# PR9022.net
KiCad netlist of a schematic drawn in EAGLE
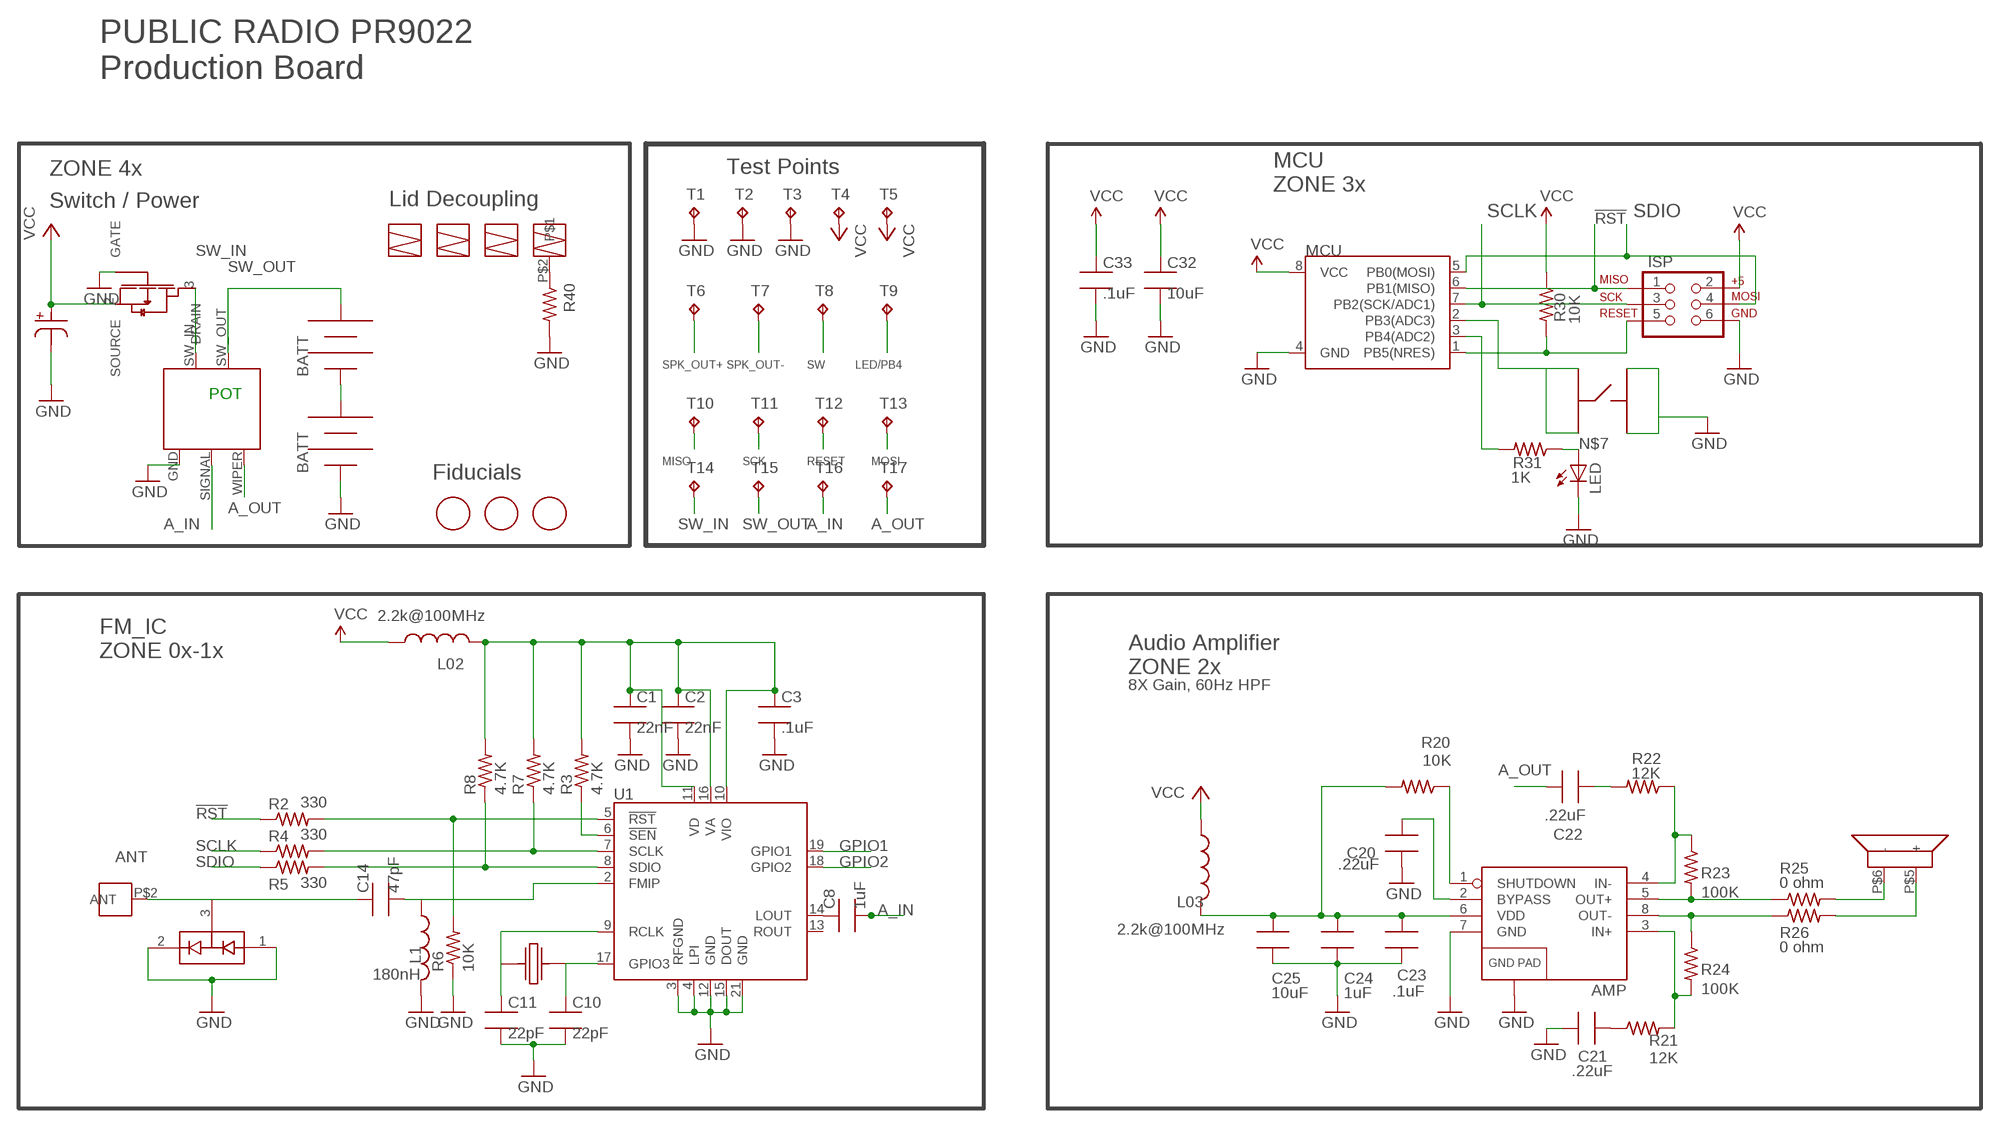
[diagram p0: schematic, sheet 1]

(export (version "E")
  (design (tool "Eeschema 10.0.6"))
  (components
    (comp (ref "AMP")
      (value "TPA6203A1")
      (footprint "eagle-import:8-MSOP")
      (libsource (lib "eagle-import") (part "TPA6203A1"))
    )
    (comp (ref "ANT_MOUNT")
      (value "DNP")
      (footprint "eagle-import:PEM_M3")
      (libsource (lib "eagle-import") (part "M3_PEMNUT"))
    )
    (comp (ref "C1")
      (value "22nF")
      (footprint "eagle-import:0603_CPL")
      (fields
        (field (name "MFG_PN") "CL10B223KB8NNNC")
        (field (name "TOL") "10%")
        (field (name "VOLTAGE") "16V")
      )
      (libsource (lib "eagle-import") (part "C_SMT_0603_CPL"))
    )
    (comp (ref "C2")
      (value "22nF")
      (footprint "eagle-import:0603_CPL")
      (fields
        (field (name "MFG_PN") "CL10B223KB8NNNC")
        (field (name "TOL") "10%")
        (field (name "VOLTAGE") "16V")
      )
      (libsource (lib "eagle-import") (part "C_SMT_0603_CPL"))
    )
    (comp (ref "C3")
      (value ".1uF")
      (footprint "eagle-import:0603_CPL")
      (fields
        (field (name "MFG_PN") "CL10B104KB8SFNC")
        (field (name "TOL") "10%")
        (field (name "VOLTAGE") "16V")
      )
      (libsource (lib "eagle-import") (part "C_SMT_0603_CPL"))
    )
    (comp (ref "C8")
      (value "1uF")
      (footprint "eagle-import:0603_CPL")
      (fields
        (field (name "MFG_PN") "CL10B105KP8NNNC")
        (field (name "TOL") "10%")
        (field (name "VOLTAGE") "10V")
      )
      (libsource (lib "eagle-import") (part "C_SMT_0603_CPL"))
    )
    (comp (ref "C10")
      (value "22pF")
      (footprint "eagle-import:0603_CPL")
      (fields
        (field (name "MFG_PN") "C1608C0G1H220J080AA")
        (field (name "TOL") "5%")
        (field (name "VOLTAGE") "50V")
      )
      (libsource (lib "eagle-import") (part "C_SMT_0603_CPL"))
    )
    (comp (ref "C11")
      (value "22pF")
      (footprint "eagle-import:0603_CPL")
      (fields
        (field (name "MFG_PN") "C1608C0G1H220J080AA")
        (field (name "TOL") "5%")
        (field (name "VOLTAGE") "50V")
      )
      (libsource (lib "eagle-import") (part "C_SMT_0603_CPL"))
    )
    (comp (ref "C14")
      (value "47pF")
      (footprint "eagle-import:0603_CPL")
      (fields
        (field (name "MFG_PN") "CL10C470JB8NCNC")
        (field (name "TOL") "5%")
        (field (name "VOLTAGE") "50V")
      )
      (libsource (lib "eagle-import") (part "C_SMT_0603_CPL"))
    )
    (comp (ref "C20")
      (value ".22uF")
      (footprint "eagle-import:0603_CPL")
      (fields
        (field (name "MFG_PN") "C1608X7R1C224K080AC")
        (field (name "TOL") "10%")
        (field (name "VOLTAGE") "16V")
      )
      (libsource (lib "eagle-import") (part "C_SMT_0603_CPL"))
    )
    (comp (ref "C21")
      (value ".22uF")
      (footprint "eagle-import:0603_CPL")
      (fields
        (field (name "MFG_PN") "C1608X7R1C224K080AC")
        (field (name "TOL") "10%")
        (field (name "VOLTAGE") "16V")
      )
      (libsource (lib "eagle-import") (part "C_SMT_0603_CPL"))
    )
    (comp (ref "C22")
      (value ".22uF")
      (footprint "eagle-import:0603_CPL")
      (fields
        (field (name "MFG_PN") "C1608X7R1C224K080AC")
        (field (name "TOL") "10%")
        (field (name "VOLTAGE") "16V")
      )
      (libsource (lib "eagle-import") (part "C_SMT_0603_CPL"))
    )
    (comp (ref "C23")
      (value ".1uF")
      (footprint "eagle-import:0603_CPL")
      (fields
        (field (name "MFG_PN") "CL10B104KB8SFNC")
        (field (name "TOL") "10%")
        (field (name "VOLTAGE") "16V")
      )
      (libsource (lib "eagle-import") (part "C_SMT_0603_CPL"))
    )
    (comp (ref "C24")
      (value "1uF")
      (footprint "eagle-import:0603_CPL")
      (fields
        (field (name "MFG_PN") "CL10B105KP8NNNC")
        (field (name "TOL") "10%")
        (field (name "VOLTAGE") "10V")
      )
      (libsource (lib "eagle-import") (part "C_SMT_0603_CPL"))
    )
    (comp (ref "C25")
      (value "10uF")
      (footprint "eagle-import:0603_CPL")
      (fields
        (field (name "MFG_PN") "CL10A106MQ8NNNC")
        (field (name "TOL") "20%")
        (field (name "VOLTAGE") "6.3V")
      )
      (libsource (lib "eagle-import") (part "C_SMT_0603_CPL"))
    )
    (comp (ref "C32")
      (value "10uF")
      (footprint "eagle-import:0603_CPL")
      (fields
        (field (name "MFG_PN") "CL10A106MQ8NNNC")
        (field (name "TOL") "20%")
        (field (name "VOLTAGE") "6.3V")
      )
      (libsource (lib "eagle-import") (part "C_SMT_0603_CPL"))
    )
    (comp (ref "C33")
      (value ".1uF")
      (footprint "eagle-import:0603_CPL")
      (fields
        (field (name "MFG_PN") "CL10B104KB8SFNC")
        (field (name "TOL") "10%")
        (field (name "VOLTAGE") "16V")
      )
      (libsource (lib "eagle-import") (part "C_SMT_0603_CPL"))
    )
    (comp (ref "C40")
      (value "220uF")
      (footprint "eagle-import:NICHICON_UD_63")
      (fields (field (name "TOL") "20%") (field (name "VOLTAGE") "16V"))
      (libsource (lib "eagle-import") (part "NICHICON_SERIESUD"))
    )
    (comp (ref "D1")
      (value "BAV99")
      (footprint "eagle-import:SOT23_CPL")
      (fields (field (name "MFG_PN") "BAV99,215"))
      (libsource (lib "eagle-import") (part "BAV99"))
    )
    (comp (ref "FET1")
      (value "AO3435")
      (footprint "eagle-import:SOT23_CPL")
      (fields (field (name "MFG_PN") "AO3435"))
      (libsource (lib "eagle-import") (part "AO3435"))
    )
    (comp (ref "ISP")
      (value "AVR_SPI_PRG_6NS")
      (footprint "eagle-import:2X3-NS")
      (libsource (lib "eagle-import") (part "AVR_SPI_PRG_6NS"))
    )
    (comp (ref "JP5")
      (value "BK-92_MPD_AA_BATT_CLIP")
      (footprint "eagle-import:BK92_AA_BATT")
      (fields (field (name "MFG_PN") "2 of BK92 - supplied by CL Labs"))
      (libsource (lib "eagle-import") (part "BK-92_MPD_AA_BATT_CLIP"))
    )
    (comp (ref "JP6")
      (value "BK-92_MPD_AA_BATT_CLIP")
      (footprint "eagle-import:BK92_AA_BATT")
      (fields (field (name "MFG_PN") "2 of BK92 - supplied by CL Labs"))
      (libsource (lib "eagle-import") (part "BK-92_MPD_AA_BATT_CLIP"))
    )
    (comp (ref "L1")
      (value "180nH")
      (footprint "eagle-import:0805_ADAFRUIT")
      (fields
        (field (name "CURRENT") "400mA")
        (field (name "DCR") "640m")
        (field (name "MFG_PN") "AISC-0805-R18J-T")
        (field (name "TOL") "5%")
      )
      (libsource (lib "eagle-import") (part "L_SMT_0805_ADAFRUIT"))
    )
    (comp (ref "L02")
      (value "2.2k@100MHz")
      (footprint "eagle-import:0603_CPL")
      (fields
        (field (name "CURRENT") "150mA")
        (field (name "DCR") "2.3")
        (field (name "MFG_PN") "HZ0603A222R-10")
      )
      (libsource (lib "eagle-import") (part "L_SMT_0603_CPL"))
    )
    (comp (ref "L03")
      (value "2.2k@100MHz")
      (footprint "eagle-import:0603_CPL")
      (fields
        (field (name "CURRENT") "150mA")
        (field (name "DCR") "2.3")
        (field (name "MFG_PN") "HZ0603A222R-10")
      )
      (libsource (lib "eagle-import") (part "L_SMT_0603_CPL"))
    )
    (comp (ref "LED")
      (value "LEDCHIPLED_0805")
      (footprint "eagle-import:CHIPLED_0805")
      (libsource (lib "eagle-import") (part "LEDCHIPLED_0805"))
    )
    (comp (ref "MARK1")
      (value "FIDUCIAL")
      (footprint "eagle-import:FIDUCIAL_1MM")
      (libsource (lib "eagle-import") (part "FIDUCIAL"))
    )
    (comp (ref "MARK2")
      (value "FIDUCIAL")
      (footprint "eagle-import:FIDUCIAL_1MM")
      (libsource (lib "eagle-import") (part "FIDUCIAL"))
    )
    (comp (ref "MARK3")
      (value "FIDUCIAL")
      (footprint "eagle-import:FIDUCIAL_1MM")
      (libsource (lib "eagle-import") (part "FIDUCIAL"))
    )
    (comp (ref "MCU")
      (value "ATTINY45TINY45-20-SMT")
      (footprint "eagle-import:8-SOIC")
      (libsource (lib "eagle-import") (part "ATTINY45TINY45-20-SMT"))
    )
    (comp (ref "R1")
      (value "RV170SF_TAIWANA_POT_SW")
      (footprint "eagle-import:RV170SF_SW_POT")
      (fields (field (name "MFG_PN") "RV170SF-43-20F-A10K - supplied by CL Labs"))
      (libsource (lib "eagle-import") (part "RV170SF_TAIWANA_POT_SW"))
    )
    (comp (ref "R2")
      (value "330")
      (footprint "eagle-import:0603_CPL")
      (fields (field (name "MFG_PN") "MCR03ERTJ331") (field (name "POWER") "1/10W") (field (name "TOL") "5%"))
      (libsource (lib "eagle-import") (part "R_SMT_R0603_CPL"))
    )
    (comp (ref "R3")
      (value "4.7K")
      (footprint "eagle-import:0603_CPL")
      (fields
        (field (name "MFG_PN") "ERJ-3EKF4701V")
        (field (name "POWER") "1/10W")
        (field (name "TOL") "1%")
      )
      (libsource (lib "eagle-import") (part "R_SMT_R0603_CPL"))
    )
    (comp (ref "R4")
      (value "330")
      (footprint "eagle-import:0603_CPL")
      (fields (field (name "MFG_PN") "MCR03ERTJ331") (field (name "POWER") "1/10W") (field (name "TOL") "5%"))
      (libsource (lib "eagle-import") (part "R_SMT_R0603_CPL"))
    )
    (comp (ref "R5")
      (value "330")
      (footprint "eagle-import:0603_CPL")
      (fields (field (name "MFG_PN") "MCR03ERTJ331") (field (name "POWER") "1/10W") (field (name "TOL") "5%"))
      (libsource (lib "eagle-import") (part "R_SMT_R0603_CPL"))
    )
    (comp (ref "R6")
      (value "10K")
      (footprint "eagle-import:0603_CPL")
      (fields
        (field (name "MFG_PN") "ERJ-3GEYJ103V")
        (field (name "POWER") "1/10W")
        (field (name "TOL") "5%")
      )
      (libsource (lib "eagle-import") (part "R_SMT_R0603_CPL"))
    )
    (comp (ref "R7")
      (value "4.7K")
      (footprint "eagle-import:0603_CPL")
      (fields
        (field (name "MFG_PN") "ERJ-3EKF4701V")
        (field (name "POWER") "1/10W")
        (field (name "TOL") "1%")
      )
      (libsource (lib "eagle-import") (part "R_SMT_R0603_CPL"))
    )
    (comp (ref "R8")
      (value "4.7K")
      (footprint "eagle-import:0603_CPL")
      (fields
        (field (name "MFG_PN") "ERJ-3EKF4701V")
        (field (name "POWER") "1/10W")
        (field (name "TOL") "1%")
      )
      (libsource (lib "eagle-import") (part "R_SMT_R0603_CPL"))
    )
    (comp (ref "R20")
      (value "10K")
      (footprint "eagle-import:0603_CPL")
      (fields
        (field (name "MFG_PN") "ERJ-3GEYJ103V")
        (field (name "POWER") "1/10W")
        (field (name "TOL") "5%")
      )
      (libsource (lib "eagle-import") (part "R_SMT_R0603_CPL"))
    )
    (comp (ref "R21")
      (value "12K")
      (footprint "eagle-import:0603_CPL")
      (fields
        (field (name "MFG_PN") "RC0603FR-0712KL")
        (field (name "POWER") "1/10W")
        (field (name "TOL") "1%")
      )
      (libsource (lib "eagle-import") (part "R_SMT_R0603_CPL"))
    )
    (comp (ref "R22")
      (value "12K")
      (footprint "eagle-import:0603_CPL")
      (fields
        (field (name "MFG_PN") "RC0603FR-0712KL")
        (field (name "POWER") "1/10W")
        (field (name "TOL") "1%")
      )
      (libsource (lib "eagle-import") (part "R_SMT_R0603_CPL"))
    )
    (comp (ref "R23")
      (value "100K")
      (footprint "eagle-import:0603_CPL")
      (fields
        (field (name "MFG_PN") "ERJ-3EKF1003V")
        (field (name "POWER") "1/10W")
        (field (name "TOL") "1%")
      )
      (libsource (lib "eagle-import") (part "R_SMT_R0603_CPL"))
    )
    (comp (ref "R24")
      (value "100K")
      (footprint "eagle-import:0603_CPL")
      (fields
        (field (name "MFG_PN") "ERJ-3EKF1003V")
        (field (name "POWER") "1/10W")
        (field (name "TOL") "1%")
      )
      (libsource (lib "eagle-import") (part "R_SMT_R0603_CPL"))
    )
    (comp (ref "R25")
      (value "0 ohm")
      (footprint "eagle-import:0805_ADAFRUIT")
      (fields (field (name "MFG_PN") "ERJ-6GEY0R00V "))
      (libsource (lib "eagle-import") (part "R_SMT_0805_ADAFRUIT"))
    )
    (comp (ref "R26")
      (value "0 ohm")
      (footprint "eagle-import:0805_ADAFRUIT")
      (fields (field (name "MFG_PN") "ERJ-6GEY0R00V "))
      (libsource (lib "eagle-import") (part "R_SMT_0805_ADAFRUIT"))
    )
    (comp (ref "R30")
      (value "10K")
      (footprint "eagle-import:0603_CPL")
      (fields
        (field (name "MFG_PN") "ERJ-3GEYJ103V")
        (field (name "POWER") "1/10W")
        (field (name "TOL") "5%")
      )
      (libsource (lib "eagle-import") (part "R_SMT_R0603_CPL"))
    )
    (comp (ref "R31")
      (value "1K")
      (footprint "eagle-import:0603_CPL")
      (fields
        (field (name "MFG_PN") "ERJ-3EKF1001V")
        (field (name "POWER") "1/10W")
        (field (name "TOL") "1%")
      )
      (libsource (lib "eagle-import") (part "R_SMT_R0603_CPL"))
    )
    (comp (ref "R40")
      (value "DNP")
      (footprint "eagle-import:0603_CPL")
      (fields (field (name "MFG_PN") "ERJ-3GEY0R00V"))
      (libsource (lib "eagle-import") (part "R_SMT_R0603_CPL"))
    )
    (comp (ref "SPKR_PLACE")
      (value "DNP")
      (footprint "eagle-import:PR2024_SPKR_PLACE")
      (libsource (lib "eagle-import") (part "PR9024_SPKR"))
    )
    (comp (ref "SW1")
      (value "C&K_PTS645")
      (footprint "eagle-import:C&K_PTS645_SMT")
      (libsource (lib "eagle-import") (part "C&K_PTS645"))
    )
    (comp (ref "T1")
      (value "TPTP20R")
      (footprint "eagle-import:TP20R")
      (libsource (lib "eagle-import") (part "TPTP20R"))
    )
    (comp (ref "T2")
      (value "TPTP20R")
      (footprint "eagle-import:TP20R")
      (libsource (lib "eagle-import") (part "TPTP20R"))
    )
    (comp (ref "T3")
      (value "TPTP20R")
      (footprint "eagle-import:TP20R")
      (libsource (lib "eagle-import") (part "TPTP20R"))
    )
    (comp (ref "T4")
      (value "TPTP20R")
      (footprint "eagle-import:TP20R")
      (libsource (lib "eagle-import") (part "TPTP20R"))
    )
    (comp (ref "T5")
      (value "TPTP20R")
      (footprint "eagle-import:TP20R")
      (libsource (lib "eagle-import") (part "TPTP20R"))
    )
    (comp (ref "T6")
      (value "TPTP20R")
      (footprint "eagle-import:TP20R")
      (libsource (lib "eagle-import") (part "TPTP20R"))
    )
    (comp (ref "T7")
      (value "TPTP20R")
      (footprint "eagle-import:TP20R")
      (libsource (lib "eagle-import") (part "TPTP20R"))
    )
    (comp (ref "T8")
      (value "TPTP20R")
      (footprint "eagle-import:TP20R")
      (libsource (lib "eagle-import") (part "TPTP20R"))
    )
    (comp (ref "T9")
      (value "TPTP20R")
      (footprint "eagle-import:TP20R")
      (libsource (lib "eagle-import") (part "TPTP20R"))
    )
    (comp (ref "T10")
      (value "TPTP20R")
      (footprint "eagle-import:TP20R")
      (libsource (lib "eagle-import") (part "TPTP20R"))
    )
    (comp (ref "T11")
      (value "TPTP20R")
      (footprint "eagle-import:TP20R")
      (libsource (lib "eagle-import") (part "TPTP20R"))
    )
    (comp (ref "T12")
      (value "TPTP20R")
      (footprint "eagle-import:TP20R")
      (libsource (lib "eagle-import") (part "TPTP20R"))
    )
    (comp (ref "T13")
      (value "TPTP20R")
      (footprint "eagle-import:TP20R")
      (libsource (lib "eagle-import") (part "TPTP20R"))
    )
    (comp (ref "T14")
      (value "TPTP20R")
      (footprint "eagle-import:TP20R")
      (libsource (lib "eagle-import") (part "TPTP20R"))
    )
    (comp (ref "T15")
      (value "TPTP20R")
      (footprint "eagle-import:TP20R")
      (libsource (lib "eagle-import") (part "TPTP20R"))
    )
    (comp (ref "T16")
      (value "TPTP20R")
      (footprint "eagle-import:TP20R")
      (libsource (lib "eagle-import") (part "TPTP20R"))
    )
    (comp (ref "T17")
      (value "TPTP20R")
      (footprint "eagle-import:TP20R")
      (libsource (lib "eagle-import") (part "TPTP20R"))
    )
    (comp (ref "U$2")
      (value "PEM_M3_NOPIN")
      (footprint "eagle-import:PEM_M3_NOKEEPAWAY")
      (libsource (lib "eagle-import") (part "PEM_M3_NOPIN"))
    )
    (comp (ref "U$3")
      (value "PEM_M3_NOPIN")
      (footprint "eagle-import:PEM_M3_NOKEEPAWAY")
      (libsource (lib "eagle-import") (part "PEM_M3_NOPIN"))
    )
    (comp (ref "U$4")
      (value "PEM_M3_NOPIN")
      (footprint "eagle-import:PEM_M3_NOKEEPAWAY")
      (libsource (lib "eagle-import") (part "PEM_M3_NOPIN"))
    )
    (comp (ref "U$5")
      (value "PEM_M3_W/PIN")
      (footprint "eagle-import:PEM_M3_NOKEEPAWAY")
      (libsource (lib "eagle-import") (part "PEM_M3_W/PIN"))
    )
    (comp (ref "U1")
      (value "SI4702-C19-GMR")
      (footprint "eagle-import:SI470X_20_QFN")
      (fields (field (name "MFG_PN") "Si4702 C19 GM - supplied by CL Labs"))
      (libsource (lib "eagle-import") (part "SI4702-C19-GMR"))
    )
    (comp (ref "X1")
      (value "ABS25XTAL")
      (footprint "eagle-import:4-SOJ")
      (libsource (lib "eagle-import") (part "ABS25XTAL"))
    )
  )
  (nets
    (net (code "1") (name "/ANT") (class "Default")
      (node (ref "ANT_MOUNT") (pin "P$2") (pinfunction "ANT_P$2") (pintype "bidirectional"))
      (node (ref "C14") (pin "1") (pinfunction "1_1") (pintype "passive"))
      (node (ref "D1") (pin "3") (pinfunction "COM_3") (pintype "bidirectional"))
    )
    (net (code "2") (name "/A_IN") (class "Default")
      (node (ref "C8") (pin "2") (pinfunction "2_2") (pintype "passive"))
      (node (ref "R1") (pin "SIGNAL") (pinfunction "SIGNAL_SIGNAL") (pintype "bidirectional"))
      (node (ref "T16") (pin "TP") (pinfunction "TP_TP") (pintype "input"))
    )
    (net (code "3") (name "/A_OUT") (class "Default")
      (node (ref "C22") (pin "2") (pinfunction "2_2") (pintype "passive"))
      (node (ref "R1") (pin "WIPER") (pinfunction "WIPER_WIPER") (pintype "bidirectional"))
      (node (ref "T17") (pin "TP") (pinfunction "TP_TP") (pintype "input"))
    )
    (net (code "4") (name "/GPIO1") (class "Default")
      (node (ref "U1") (pin "19") (pinfunction "GPIO1_19") (pintype "bidirectional"))
    )
    (net (code "5") (name "/GPIO2") (class "Default")
      (node (ref "U1") (pin "18") (pinfunction "GPIO2_18") (pintype "bidirectional"))
    )
    (net (code "6") (name "/LED{slash}PB4") (class "Default")
      (node (ref "MCU") (pin "3") (pinfunction "PB4(ADC2)_3") (pintype "bidirectional"))
      (node (ref "R31") (pin "2") (pinfunction "2_2") (pintype "passive"))
      (node (ref "T9") (pin "TP") (pinfunction "TP_TP") (pintype "input"))
    )
    (net (code "7") (name "/N$7") (class "Default")
      (node (ref "LED") (pin "A") (pinfunction "A_A") (pintype "passive"))
      (node (ref "R31") (pin "1") (pinfunction "1_1") (pintype "passive"))
    )
    (net (code "8") (name "/RESET") (class "Default")
      (node (ref "ISP") (pin "5") (pinfunction "5_5") (pintype "passive"))
      (node (ref "MCU") (pin "1") (pinfunction "PB5(NRES)_1") (pintype "bidirectional"))
      (node (ref "R30") (pin "2") (pinfunction "2_2") (pintype "passive"))
      (node (ref "T12") (pin "TP") (pinfunction "TP_TP") (pintype "input"))
    )
    (net (code "9") (name "/SCLK") (class "Default")
      (node (ref "ISP") (pin "3") (pinfunction "3_3") (pintype "passive"))
      (node (ref "MCU") (pin "7") (pinfunction "PB2(SCK/ADC1)_7") (pintype "bidirectional"))
      (node (ref "R4") (pin "1") (pinfunction "1_1") (pintype "passive"))
      (node (ref "T11") (pin "TP") (pinfunction "TP_TP") (pintype "input"))
    )
    (net (code "10") (name "/SDIO") (class "Default")
      (node (ref "ISP") (pin "4") (pinfunction "4_4") (pintype "passive"))
      (node (ref "MCU") (pin "5") (pinfunction "PB0(MOSI)_5") (pintype "bidirectional"))
      (node (ref "R5") (pin "1") (pinfunction "1_1") (pintype "passive"))
      (node (ref "T13") (pin "TP") (pinfunction "TP_TP") (pintype "input"))
    )
    (net (code "11") (name "/SPK_OUT+") (class "Default")
      (node (ref "R25") (pin "2") (pinfunction "2_2") (pintype "passive"))
      (node (ref "SPKR_PLACE") (pin "P$6") (pinfunction "-_P$6") (pintype "bidirectional"))
      (node (ref "T6") (pin "TP") (pinfunction "TP_TP") (pintype "input"))
    )
    (net (code "12") (name "/SPK_OUT-") (class "Default")
      (node (ref "R26") (pin "2") (pinfunction "2_2") (pintype "passive"))
      (node (ref "SPKR_PLACE") (pin "P$5") (pinfunction "+_P$5") (pintype "bidirectional"))
      (node (ref "T7") (pin "TP") (pinfunction "TP_TP") (pintype "input"))
    )
    (net (code "13") (name "/SW") (class "Default")
      (node (ref "MCU") (pin "2") (pinfunction "PB3(ADC3)_2") (pintype "bidirectional"))
      (node (ref "SW1") (pin "P$3") (pinfunction "P$3_P$3") (pintype "bidirectional"))
      (node (ref "SW1") (pin "P$4") (pinfunction "P$4_P$4") (pintype "bidirectional"))
      (node (ref "T8") (pin "TP") (pinfunction "TP_TP") (pintype "input"))
    )
    (net (code "14") (name "/SW_IN") (class "Default")
      (node (ref "FET1") (pin "3") (pinfunction "DRAIN_3") (pintype "bidirectional"))
      (node (ref "R1") (pin "SW_IN") (pinfunction "SW_IN_SW_IN") (pintype "bidirectional"))
      (node (ref "T14") (pin "TP") (pinfunction "TP_TP") (pintype "input"))
    )
    (net (code "15") (name "/SW_OUT") (class "Default")
      (node (ref "JP5") (pin "POS") (pinfunction "POS_POS") (pintype "bidirectional"))
      (node (ref "JP5") (pin "POS@2") (pinfunction "POS_POS@2") (pintype "bidirectional"))
      (node (ref "R1") (pin "SW_OUT") (pinfunction "SW_OUT_SW_OUT") (pintype "bidirectional"))
      (node (ref "T15") (pin "TP") (pinfunction "TP_TP") (pintype "input"))
    )
    (net (code "16") (name "/~{RST}") (class "Default")
      (node (ref "ISP") (pin "1") (pinfunction "1_1") (pintype "passive"))
      (node (ref "MCU") (pin "6") (pinfunction "PB1(MISO)_6") (pintype "bidirectional"))
      (node (ref "R2") (pin "1") (pinfunction "1_1") (pintype "passive"))
      (node (ref "T10") (pin "TP") (pinfunction "TP_TP") (pintype "input"))
    )
    (net (code "17") (name "GND") (class "Default")
      (node (ref "AMP") (pin "7") (pinfunction "GND_7") (pintype "power_in"))
      (node (ref "AMP") (pin "9") (pinfunction "GND_9") (pintype "power_in"))
      (node (ref "C1") (pin "2") (pinfunction "2_2") (pintype "passive"))
      (node (ref "C10") (pin "2") (pinfunction "2_2") (pintype "passive"))
      (node (ref "C11") (pin "2") (pinfunction "2_2") (pintype "passive"))
      (node (ref "C2") (pin "2") (pinfunction "2_2") (pintype "passive"))
      (node (ref "C20") (pin "1") (pinfunction "1_1") (pintype "passive"))
      (node (ref "C21") (pin "1") (pinfunction "1_1") (pintype "passive"))
      (node (ref "C23") (pin "2") (pinfunction "2_2") (pintype "passive"))
      (node (ref "C24") (pin "2") (pinfunction "2_2") (pintype "passive"))
      (node (ref "C25") (pin "2") (pinfunction "2_2") (pintype "passive"))
      (node (ref "C3") (pin "2") (pinfunction "2_2") (pintype "passive"))
      (node (ref "C32") (pin "2") (pinfunction "2_2") (pintype "passive"))
      (node (ref "C33") (pin "2") (pinfunction "2_2") (pintype "passive"))
      (node (ref "C40") (pin "P$2") (pinfunction "P$2_P$2") (pintype "bidirectional"))
      (node (ref "D1") (pin "1") (pinfunction "A1_1") (pintype "bidirectional"))
      (node (ref "D1") (pin "2") (pinfunction "C2_2") (pintype "bidirectional"))
      (node (ref "FET1") (pin "1") (pinfunction "GATE_1") (pintype "bidirectional"))
      (node (ref "ISP") (pin "6") (pinfunction "6_6") (pintype "passive"))
      (node (ref "JP6") (pin "NEG") (pinfunction "NEG_NEG") (pintype "bidirectional"))
      (node (ref "JP6") (pin "NEG@2") (pinfunction "NEG_NEG@2") (pintype "bidirectional"))
      (node (ref "L1") (pin "2") (pinfunction "2_2") (pintype "passive"))
      (node (ref "LED") (pin "C") (pinfunction "C_C") (pintype "passive"))
      (node (ref "MCU") (pin "4") (pinfunction "GND_4") (pintype "bidirectional"))
      (node (ref "R1") (pin "GND") (pinfunction "GND_GND") (pintype "bidirectional"))
      (node (ref "R40") (pin "2") (pinfunction "2_2") (pintype "passive"))
      (node (ref "R6") (pin "1") (pinfunction "1_1") (pintype "passive"))
      (node (ref "SW1") (pin "P$1") (pinfunction "P$1_P$1") (pintype "bidirectional"))
      (node (ref "SW1") (pin "P$2") (pinfunction "P$2_P$2") (pintype "bidirectional"))
      (node (ref "T1") (pin "TP") (pinfunction "TP_TP") (pintype "input"))
      (node (ref "T2") (pin "TP") (pinfunction "TP_TP") (pintype "input"))
      (node (ref "T3") (pin "TP") (pinfunction "TP_TP") (pintype "input"))
      (node (ref "U1") (pin "12") (pinfunction "GND_12") (pintype "bidirectional"))
      (node (ref "U1") (pin "15") (pinfunction "DOUT_15") (pintype "bidirectional"))
      (node (ref "U1") (pin "21") (pinfunction "GND_21") (pintype "bidirectional"))
      (node (ref "U1") (pin "3") (pinfunction "RFGND_3") (pintype "bidirectional"))
      (node (ref "U1") (pin "4") (pinfunction "LPI_4") (pintype "bidirectional"))
    )
    (net (code "18") (name "Net-(AMP-BYPASS)") (class "Default")
      (node (ref "AMP") (pin "2") (pinfunction "BYPASS_2") (pintype "bidirectional"))
      (node (ref "C20") (pin "2") (pinfunction "2_2") (pintype "passive"))
    )
    (net (code "19") (name "Net-(AMP-IN+)") (class "Default")
      (node (ref "AMP") (pin "3") (pinfunction "IN+_3") (pintype "bidirectional"))
      (node (ref "R21") (pin "2") (pinfunction "2_2") (pintype "passive"))
      (node (ref "R24") (pin "2") (pinfunction "2_2") (pintype "passive"))
    )
    (net (code "20") (name "Net-(AMP-IN-)") (class "Default")
      (node (ref "AMP") (pin "4") (pinfunction "IN-_4") (pintype "bidirectional"))
      (node (ref "R22") (pin "1") (pinfunction "1_1") (pintype "passive"))
      (node (ref "R23") (pin "1") (pinfunction "1_1") (pintype "passive"))
    )
    (net (code "21") (name "Net-(AMP-OUT+)") (class "Default")
      (node (ref "AMP") (pin "5") (pinfunction "OUT+_5") (pintype "bidirectional"))
      (node (ref "R23") (pin "2") (pinfunction "2_2") (pintype "passive"))
      (node (ref "R25") (pin "1") (pinfunction "1_1") (pintype "passive"))
    )
    (net (code "22") (name "Net-(AMP-OUT-)") (class "Default")
      (node (ref "AMP") (pin "8") (pinfunction "OUT-_8") (pintype "bidirectional"))
      (node (ref "R24") (pin "1") (pinfunction "1_1") (pintype "passive"))
      (node (ref "R26") (pin "1") (pinfunction "1_1") (pintype "passive"))
    )
    (net (code "23") (name "Net-(AMP-SHUTDOWN)") (class "Default")
      (node (ref "AMP") (pin "1") (pinfunction "SHUTDOWN_1") (pintype "input"))
      (node (ref "R20") (pin "1") (pinfunction "1_1") (pintype "passive"))
    )
    (net (code "24") (name "Net-(AMP-VDD)") (class "Default")
      (node (ref "AMP") (pin "6") (pinfunction "VDD_6") (pintype "power_in"))
      (node (ref "C23") (pin "1") (pinfunction "1_1") (pintype "passive"))
      (node (ref "C24") (pin "1") (pinfunction "1_1") (pintype "passive"))
      (node (ref "C25") (pin "1") (pinfunction "1_1") (pintype "passive"))
      (node (ref "L03") (pin "2") (pinfunction "2_2") (pintype "passive"))
      (node (ref "R20") (pin "2") (pinfunction "2_2") (pintype "passive"))
    )
    (net (code "25") (name "Net-(C21-Pad2)") (class "Default")
      (node (ref "C21") (pin "2") (pinfunction "2_2") (pintype "passive"))
      (node (ref "R21") (pin "1") (pinfunction "1_1") (pintype "passive"))
    )
    (net (code "26") (name "Net-(C22-Pad1)") (class "Default")
      (node (ref "C22") (pin "1") (pinfunction "1_1") (pintype "passive"))
      (node (ref "R22") (pin "2") (pinfunction "2_2") (pintype "passive"))
    )
    (net (code "27") (name "Net-(JP5-NEG-PadNEG@2)") (class "Default")
      (node (ref "JP5") (pin "NEG") (pinfunction "NEG_NEG") (pintype "bidirectional"))
      (node (ref "JP5") (pin "NEG@2") (pinfunction "NEG_NEG@2") (pintype "bidirectional"))
      (node (ref "JP6") (pin "POS") (pinfunction "POS_POS") (pintype "bidirectional"))
      (node (ref "JP6") (pin "POS@2") (pinfunction "POS_POS@2") (pintype "bidirectional"))
    )
    (net (code "28") (name "Net-(U$5-P$1)") (class "Default")
      (node (ref "R40") (pin "1") (pinfunction "1_1") (pintype "passive"))
      (node (ref "U$5") (pin "P$2") (pinfunction "P$1_P$2") (pintype "bidirectional"))
    )
    (net (code "29") (name "Net-(U1-FMIP)") (class "Default")
      (node (ref "C14") (pin "2") (pinfunction "2_2") (pintype "passive"))
      (node (ref "L1") (pin "1") (pinfunction "1_1") (pintype "passive"))
      (node (ref "U1") (pin "2") (pinfunction "FMIP_2") (pintype "bidirectional"))
    )
    (net (code "30") (name "Net-(U1-GPIO3)") (class "Default")
      (node (ref "C10") (pin "1") (pinfunction "1_1") (pintype "passive"))
      (node (ref "U1") (pin "17") (pinfunction "GPIO3_17") (pintype "bidirectional"))
      (node (ref "X1") (pin "P$4") (pinfunction "P$4_P$4") (pintype "bidirectional"))
    )
    (net (code "31") (name "Net-(U1-LOUT)") (class "Default")
      (node (ref "C8") (pin "1") (pinfunction "1_1") (pintype "passive"))
      (node (ref "U1") (pin "14") (pinfunction "LOUT_14") (pintype "bidirectional"))
    )
    (net (code "32") (name "Net-(U1-RCLK)") (class "Default")
      (node (ref "C11") (pin "1") (pinfunction "1_1") (pintype "passive"))
      (node (ref "U1") (pin "9") (pinfunction "RCLK_9") (pintype "bidirectional"))
      (node (ref "X1") (pin "P$1") (pinfunction "P$1_P$1") (pintype "bidirectional"))
    )
    (net (code "33") (name "Net-(U1-SCLK)") (class "Default")
      (node (ref "R4") (pin "2") (pinfunction "2_2") (pintype "passive"))
      (node (ref "R7") (pin "1") (pinfunction "1_1") (pintype "passive"))
      (node (ref "U1") (pin "7") (pinfunction "SCLK_7") (pintype "bidirectional"))
    )
    (net (code "34") (name "Net-(U1-SDIO)") (class "Default")
      (node (ref "R5") (pin "2") (pinfunction "2_2") (pintype "passive"))
      (node (ref "R8") (pin "1") (pinfunction "1_1") (pintype "passive"))
      (node (ref "U1") (pin "8") (pinfunction "SDIO_8") (pintype "bidirectional"))
    )
    (net (code "35") (name "Net-(U1-VA)") (class "Default")
      (node (ref "C1") (pin "1") (pinfunction "1_1") (pintype "passive"))
      (node (ref "C2") (pin "1") (pinfunction "1_1") (pintype "passive"))
      (node (ref "C3") (pin "1") (pinfunction "1_1") (pintype "passive"))
      (node (ref "L02") (pin "2") (pinfunction "2_2") (pintype "passive"))
      (node (ref "R3") (pin "2") (pinfunction "2_2") (pintype "passive"))
      (node (ref "R7") (pin "2") (pinfunction "2_2") (pintype "passive"))
      (node (ref "R8") (pin "2") (pinfunction "2_2") (pintype "passive"))
      (node (ref "U1") (pin "10") (pinfunction "VIO_10") (pintype "bidirectional"))
      (node (ref "U1") (pin "11") (pinfunction "VD_11") (pintype "bidirectional"))
      (node (ref "U1") (pin "16") (pinfunction "VA_16") (pintype "bidirectional"))
    )
    (net (code "36") (name "Net-(U1-~{RST})") (class "Default")
      (node (ref "R2") (pin "2") (pinfunction "2_2") (pintype "passive"))
      (node (ref "R6") (pin "2") (pinfunction "2_2") (pintype "passive"))
      (node (ref "U1") (pin "5") (pinfunction "~{RST}_5") (pintype "bidirectional"))
    )
    (net (code "37") (name "Net-(U1-~{SEN})") (class "Default")
      (node (ref "R3") (pin "1") (pinfunction "1_1") (pintype "passive"))
      (node (ref "U1") (pin "6") (pinfunction "~{SEN}_6") (pintype "bidirectional"))
    )
    (net (code "38") (name "VCC") (class "Default")
      (node (ref "C32") (pin "1") (pinfunction "1_1") (pintype "passive"))
      (node (ref "C33") (pin "1") (pinfunction "1_1") (pintype "passive"))
      (node (ref "C40") (pin "P$1") (pinfunction "P$1_P$1") (pintype "bidirectional"))
      (node (ref "FET1") (pin "2") (pinfunction "SOURCE_2") (pintype "bidirectional"))
      (node (ref "ISP") (pin "2") (pinfunction "2_2") (pintype "passive"))
      (node (ref "L02") (pin "1") (pinfunction "1_1") (pintype "passive"))
      (node (ref "L03") (pin "1") (pinfunction "1_1") (pintype "passive"))
      (node (ref "MCU") (pin "8") (pinfunction "VCC_8") (pintype "bidirectional"))
      (node (ref "R30") (pin "1") (pinfunction "1_1") (pintype "passive"))
      (node (ref "T4") (pin "TP") (pinfunction "TP_TP") (pintype "input"))
      (node (ref "T5") (pin "TP") (pinfunction "TP_TP") (pintype "input"))
    )
    (net (code "39") (name "unconnected-(U1-ROUT-Pad13)") (class "Default")
      (node (ref "U1") (pin "13") (pinfunction "ROUT_13") (pintype "bidirectional"))
    )
  )
)
